# SMC_FrontPanel_ExtensionBoardV8_SMD.net
KiCad netlist of a schematic drawn in EAGLE
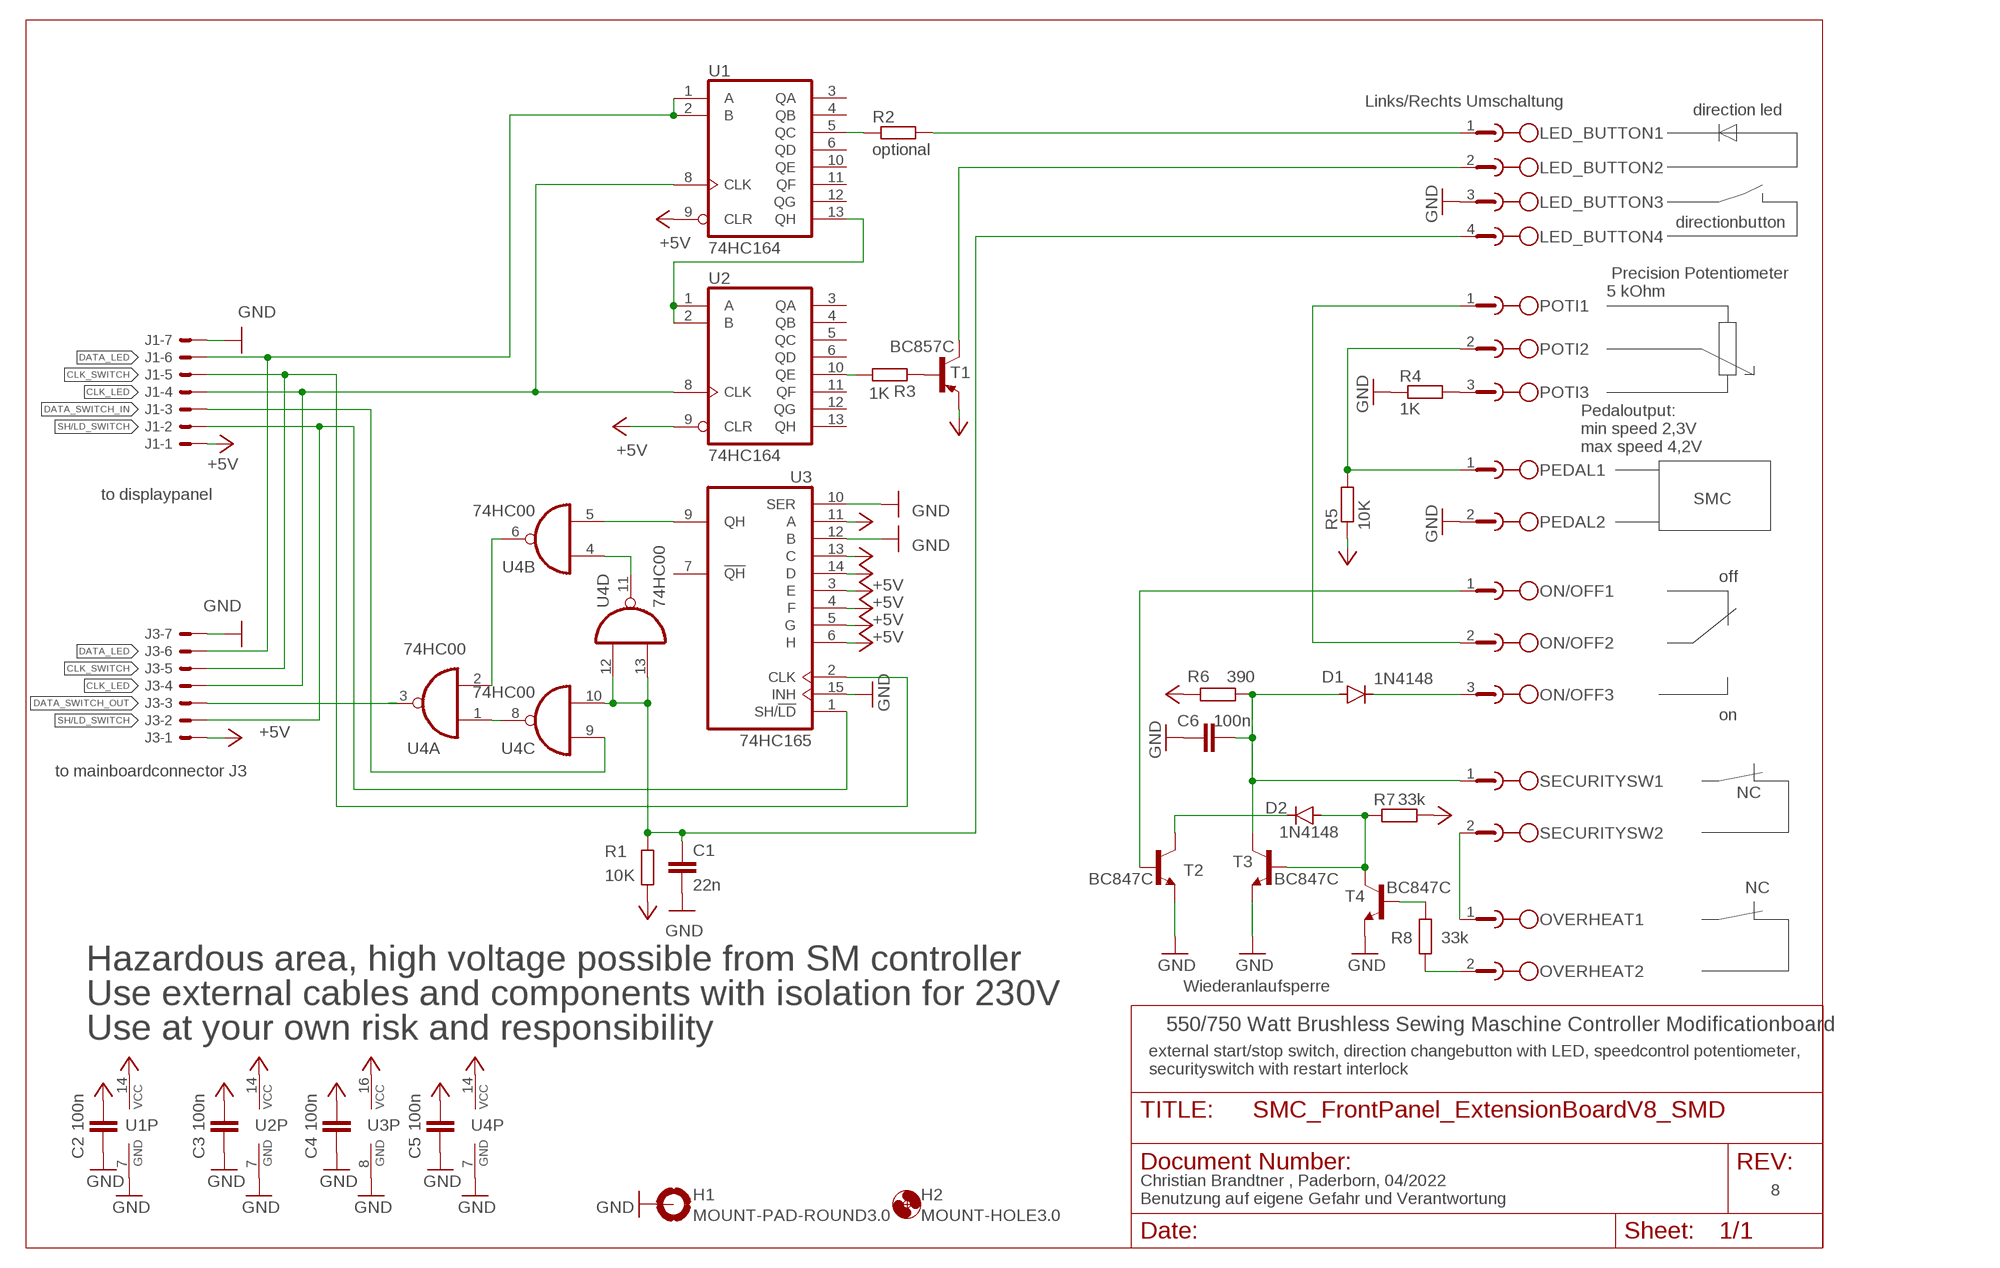
[diagram p0: schematic, sheet 1]

(export (version "E")
  (design (tool "Eeschema 10.0.6"))
  (components
    (comp (ref "C1")
      (value "22n")
      (footprint "eagle-import:C0805")
      (libsource (lib "eagle-import") (part "C-EUC0805"))
    )
    (comp (ref "C2")
      (value "100n")
      (footprint "eagle-import:C0805")
      (libsource (lib "eagle-import") (part "C-EUC0805"))
    )
    (comp (ref "C3")
      (value "100n")
      (footprint "eagle-import:C0805")
      (libsource (lib "eagle-import") (part "C-EUC0805"))
    )
    (comp (ref "C4")
      (value "100n")
      (footprint "eagle-import:C0805")
      (libsource (lib "eagle-import") (part "C-EUC0805"))
    )
    (comp (ref "C5")
      (value "100n")
      (footprint "eagle-import:C0805")
      (libsource (lib "eagle-import") (part "C-EUC0805"))
    )
    (comp (ref "C6")
      (value "100n")
      (footprint "eagle-import:C0805")
      (libsource (lib "eagle-import") (part "C-EUC0805"))
    )
    (comp (ref "D1")
      (value "1N4148")
      (footprint "eagle-import:SOD323-W")
      (libsource (lib "eagle-import") (part "DIODE-SOD323-W"))
    )
    (comp (ref "D2")
      (value "1N4148")
      (footprint "eagle-import:SOD323-W")
      (libsource (lib "eagle-import") (part "DIODE-SOD323-W"))
    )
    (comp (ref "H1")
      (value "MOUNT-PAD-ROUND3.0")
      (footprint "eagle-import:3,0-PAD")
      (libsource (lib "eagle-import") (part "MOUNT-PAD-ROUND3.0"))
    )
    (comp (ref "H2")
      (value "MOUNT-HOLE3.0")
      (footprint "eagle-import:3,0")
      (libsource (lib "eagle-import") (part "MOUNT-HOLE3.0"))
    )
    (comp (ref "J1")
      (value "to displaypanel")
      (footprint "eagle-import:JST-XH-07-PACKAGE-ROUND-PAD")
      (libsource (lib "eagle-import") (part "JST-XH-07-PIN-ROUND-PAD"))
    )
    (comp (ref "J3")
      (value "to mainboardconnector J3")
      (footprint "eagle-import:JST-XH-07-PACKAGE-ROUND-PAD")
      (libsource (lib "eagle-import") (part "JST-XH-07-PIN-ROUND-PAD"))
    )
    (comp (ref "LED_BUTTON")
      (value "MC_1.5/4_G_3.5")
      (footprint "eagle-import:MC_1.5_4-G-3.5")
      (libsource (lib "eagle-import") (part "MC_1.5/4_G_3.5"))
    )
    (comp (ref "ON/OFF")
      (value "MC_1.5/3-G-3.5")
      (footprint "eagle-import:MC_1.5_3-G-3.5")
      (libsource (lib "eagle-import") (part "MC_1.5/3-G-3.5"))
    )
    (comp (ref "OVERHEAT")
      (value "MC_1.5/2-G-3.5")
      (footprint "eagle-import:MC_1.5_2-G-3.5")
      (libsource (lib "eagle-import") (part "MC_1.5/2-G-3.5"))
    )
    (comp (ref "PEDAL")
      (value "MC_1.5/2-G-3.5")
      (footprint "eagle-import:MC_1.5_2-G-3.5")
      (libsource (lib "eagle-import") (part "MC_1.5/2-G-3.5"))
    )
    (comp (ref "POTI")
      (value "MC_1.5/3-G-3.5")
      (footprint "eagle-import:MC_1.5_3-G-3.5")
      (libsource (lib "eagle-import") (part "MC_1.5/3-G-3.5"))
    )
    (comp (ref "R1")
      (value "10K")
      (footprint "eagle-import:R0805")
      (libsource (lib "eagle-import") (part "R-EU_R0805"))
    )
    (comp (ref "R2")
      (value "optional")
      (footprint "eagle-import:R0805")
      (libsource (lib "eagle-import") (part "R-EU_R0805"))
    )
    (comp (ref "R3")
      (value "1K")
      (footprint "eagle-import:R0805")
      (libsource (lib "eagle-import") (part "R-EU_R0805"))
    )
    (comp (ref "R4")
      (value "1K")
      (footprint "eagle-import:R0805")
      (libsource (lib "eagle-import") (part "R-EU_R0805"))
    )
    (comp (ref "R5")
      (value "10K")
      (footprint "eagle-import:R0805")
      (libsource (lib "eagle-import") (part "R-EU_R0805"))
    )
    (comp (ref "R6")
      (value "390")
      (footprint "eagle-import:R0805")
      (libsource (lib "eagle-import") (part "R-EU_R0805"))
    )
    (comp (ref "R7")
      (value "33k")
      (footprint "eagle-import:R0805")
      (libsource (lib "eagle-import") (part "R-EU_R0805"))
    )
    (comp (ref "R8")
      (value "33k")
      (footprint "eagle-import:R0805")
      (libsource (lib "eagle-import") (part "R-EU_R0805"))
    )
    (comp (ref "SECURITYSW")
      (value "MC_1.5/2-G-3.5")
      (footprint "eagle-import:MC_1.5_2-G-3.5")
      (libsource (lib "eagle-import") (part "MC_1.5/2-G-3.5"))
    )
    (comp (ref "T1")
      (value "BC857C")
      (footprint "eagle-import:SOT23-BEC")
      (libsource (lib "eagle-import") (part "-PNP-SOT23-BECBC857C"))
    )
    (comp (ref "T2")
      (value "BC847C")
      (footprint "eagle-import:SOT23-BEC")
      (libsource (lib "eagle-import") (part "-NPN-SOT23-BECBC847C"))
    )
    (comp (ref "T3")
      (value "BC847C")
      (footprint "eagle-import:SOT23-BEC")
      (libsource (lib "eagle-import") (part "-NPN-SOT23-BECBC847C"))
    )
    (comp (ref "T4")
      (value "BC847C")
      (footprint "eagle-import:SOT23-BEC")
      (libsource (lib "eagle-import") (part "-NPN-SOT23-BECBC847C"))
    )
    (comp (ref "U1")
      (value "74HC164")
      (footprint "eagle-import:SO14")
      (libsource (lib "eagle-import") (part "74164DHC"))
    )
    (comp (ref "U2")
      (value "74HC164")
      (footprint "eagle-import:SO14")
      (libsource (lib "eagle-import") (part "74164DHC"))
    )
    (comp (ref "U3")
      (value "74HC165")
      (footprint "eagle-import:SO16")
      (libsource (lib "eagle-import") (part "74165DHC"))
    )
    (comp (ref "U4")
      (value "74HC00")
      (footprint "eagle-import:SO14")
      (libsource (lib "eagle-import") (part "7400DHC"))
    )
  )
  (nets
    (net (code "1") (name "+5V") (class "Default")
      (node (ref "C2") (pin "2") (pinfunction "2_2") (pintype "passive"))
      (node (ref "C3") (pin "2") (pinfunction "2_2") (pintype "passive"))
      (node (ref "C4") (pin "2") (pinfunction "2_2") (pintype "passive"))
      (node (ref "C5") (pin "2") (pinfunction "2_2") (pintype "passive"))
      (node (ref "J1") (pin "1") (pinfunction "S_1") (pintype "passive"))
      (node (ref "J3") (pin "1") (pinfunction "S_1") (pintype "passive"))
      (node (ref "R1") (pin "2") (pinfunction "2_2") (pintype "passive"))
      (node (ref "R5") (pin "1") (pinfunction "1_1") (pintype "passive"))
      (node (ref "R6") (pin "2") (pinfunction "2_2") (pintype "passive"))
      (node (ref "R7") (pin "1") (pinfunction "1_1") (pintype "passive"))
      (node (ref "T1") (pin "E") (pinfunction "E_E") (pintype "passive"))
      (node (ref "U1") (pin "14") (pinfunction "VCC_14") (pintype "power_in"))
      (node (ref "U1") (pin "9") (pinfunction "CLR_9") (pintype "input"))
      (node (ref "U2") (pin "14") (pinfunction "VCC_14") (pintype "power_in"))
      (node (ref "U2") (pin "9") (pinfunction "CLR_9") (pintype "input"))
      (node (ref "U3") (pin "11") (pinfunction "A_11") (pintype "input"))
      (node (ref "U3") (pin "13") (pinfunction "C_13") (pintype "input"))
      (node (ref "U3") (pin "14") (pinfunction "D_14") (pintype "input"))
      (node (ref "U3") (pin "16") (pinfunction "VCC_16") (pintype "power_in"))
      (node (ref "U3") (pin "3") (pinfunction "E_3") (pintype "input"))
      (node (ref "U3") (pin "4") (pinfunction "F_4") (pintype "input"))
      (node (ref "U3") (pin "5") (pinfunction "G_5") (pintype "input"))
      (node (ref "U3") (pin "6") (pinfunction "H_6") (pintype "input"))
      (node (ref "U4") (pin "14") (pinfunction "VCC_14") (pintype "power_in"))
    )
    (net (code "2") (name "CLK_LED") (class "Default")
      (node (ref "J1") (pin "4") (pinfunction "S_4") (pintype "passive"))
      (node (ref "J3") (pin "4") (pinfunction "S_4") (pintype "passive"))
      (node (ref "U1") (pin "8") (pinfunction "CLK_8") (pintype "input"))
      (node (ref "U2") (pin "8") (pinfunction "CLK_8") (pintype "input"))
    )
    (net (code "3") (name "CLK_SWITCH") (class "Default")
      (node (ref "J1") (pin "5") (pinfunction "S_5") (pintype "passive"))
      (node (ref "J3") (pin "5") (pinfunction "S_5") (pintype "passive"))
      (node (ref "U3") (pin "2") (pinfunction "CLK_2") (pintype "input"))
    )
    (net (code "4") (name "DATA_LED") (class "Default")
      (node (ref "J1") (pin "6") (pinfunction "S_6") (pintype "passive"))
      (node (ref "J3") (pin "6") (pinfunction "S_6") (pintype "passive"))
      (node (ref "U1") (pin "1") (pinfunction "A_1") (pintype "input"))
      (node (ref "U1") (pin "2") (pinfunction "B_2") (pintype "input"))
    )
    (net (code "5") (name "DATA_SWITCH_IN") (class "Default")
      (node (ref "J1") (pin "3") (pinfunction "S_3") (pintype "passive"))
      (node (ref "U4") (pin "9") (pinfunction "I0_9") (pintype "input"))
    )
    (net (code "6") (name "DATA_SWITCH_OUT") (class "Default")
      (node (ref "J3") (pin "3") (pinfunction "S_3") (pintype "passive"))
      (node (ref "U4") (pin "3") (pinfunction "O_3") (pintype "output"))
    )
    (net (code "7") (name "GND") (class "Default")
      (node (ref "C1") (pin "2") (pinfunction "2_2") (pintype "passive"))
      (node (ref "C2") (pin "1") (pinfunction "1_1") (pintype "passive"))
      (node (ref "C3") (pin "1") (pinfunction "1_1") (pintype "passive"))
      (node (ref "C4") (pin "1") (pinfunction "1_1") (pintype "passive"))
      (node (ref "C5") (pin "1") (pinfunction "1_1") (pintype "passive"))
      (node (ref "C6") (pin "1") (pinfunction "1_1") (pintype "passive"))
      (node (ref "H1") (pin "B3,0") (pinfunction "MOUNT_B3,0") (pintype "passive"))
      (node (ref "J1") (pin "7") (pinfunction "S_7") (pintype "passive"))
      (node (ref "J3") (pin "7") (pinfunction "S_7") (pintype "passive"))
      (node (ref "LED_BUTTON") (pin "3") (pinfunction "1_3") (pintype "passive"))
      (node (ref "PEDAL") (pin "2") (pinfunction "1_2") (pintype "passive"))
      (node (ref "R4") (pin "1") (pinfunction "1_1") (pintype "passive"))
      (node (ref "T2") (pin "E") (pinfunction "E_E") (pintype "passive"))
      (node (ref "T3") (pin "E") (pinfunction "E_E") (pintype "passive"))
      (node (ref "T4") (pin "E") (pinfunction "E_E") (pintype "passive"))
      (node (ref "U1") (pin "7") (pinfunction "GND_7") (pintype "power_in"))
      (node (ref "U2") (pin "7") (pinfunction "GND_7") (pintype "power_in"))
      (node (ref "U3") (pin "10") (pinfunction "SER_10") (pintype "input"))
      (node (ref "U3") (pin "12") (pinfunction "B_12") (pintype "input"))
      (node (ref "U3") (pin "15") (pinfunction "INH_15") (pintype "input"))
      (node (ref "U3") (pin "8") (pinfunction "GND_8") (pintype "power_in"))
      (node (ref "U4") (pin "7") (pinfunction "GND_7") (pintype "power_in"))
    )
    (net (code "8") (name "Net-(C6-Pad2)") (class "Default")
      (node (ref "C6") (pin "2") (pinfunction "2_2") (pintype "passive"))
      (node (ref "D1") (pin "A") (pinfunction "A_A") (pintype "passive"))
      (node (ref "R6") (pin "1") (pinfunction "1_1") (pintype "passive"))
      (node (ref "SECURITYSW") (pin "1") (pinfunction "1_1") (pintype "passive"))
      (node (ref "T3") (pin "C") (pinfunction "C_C") (pintype "passive"))
    )
    (net (code "9") (name "Net-(D2-PadA)") (class "Default")
      (node (ref "D2") (pin "A") (pinfunction "A_A") (pintype "passive"))
      (node (ref "R7") (pin "2") (pinfunction "2_2") (pintype "passive"))
      (node (ref "T3") (pin "B") (pinfunction "B_B") (pintype "passive"))
      (node (ref "T4") (pin "C") (pinfunction "C_C") (pintype "passive"))
    )
    (net (code "10") (name "Net-(D2-PadC)") (class "Default")
      (node (ref "D2") (pin "C") (pinfunction "C_C") (pintype "passive"))
      (node (ref "T2") (pin "C") (pinfunction "C_C") (pintype "passive"))
    )
    (net (code "11") (name "Net-(LED_BUTTON-Pad1)") (class "Default")
      (node (ref "LED_BUTTON") (pin "1") (pinfunction "1_1") (pintype "passive"))
      (node (ref "R2") (pin "2") (pinfunction "2_2") (pintype "passive"))
    )
    (net (code "12") (name "Net-(LED_BUTTONB-1)") (class "Default")
      (node (ref "LED_BUTTON") (pin "2") (pinfunction "1_2") (pintype "passive"))
      (node (ref "T1") (pin "C") (pinfunction "C_C") (pintype "passive"))
    )
    (net (code "13") (name "Net-(LED_BUTTOND-1)") (class "Default")
      (node (ref "C1") (pin "1") (pinfunction "1_1") (pintype "passive"))
      (node (ref "LED_BUTTON") (pin "4") (pinfunction "1_4") (pintype "passive"))
      (node (ref "R1") (pin "1") (pinfunction "1_1") (pintype "passive"))
      (node (ref "U4") (pin "10") (pinfunction "I1_10") (pintype "input"))
      (node (ref "U4") (pin "12") (pinfunction "I0_12") (pintype "input"))
      (node (ref "U4") (pin "13") (pinfunction "I1_13") (pintype "input"))
    )
    (net (code "14") (name "Net-(ON/OFF-Pad1)") (class "Default")
      (node (ref "ON/OFF") (pin "1") (pinfunction "1_1") (pintype "passive"))
      (node (ref "T2") (pin "B") (pinfunction "B_B") (pintype "passive"))
    )
    (net (code "15") (name "Net-(ON/OFFB-1)") (class "Default")
      (node (ref "ON/OFF") (pin "2") (pinfunction "1_2") (pintype "passive"))
      (node (ref "POTI") (pin "1") (pinfunction "1_1") (pintype "passive"))
    )
    (net (code "16") (name "Net-(ON/OFFC-1)") (class "Default")
      (node (ref "D1") (pin "C") (pinfunction "C_C") (pintype "passive"))
      (node (ref "ON/OFF") (pin "3") (pinfunction "1_3") (pintype "passive"))
    )
    (net (code "17") (name "Net-(OVERHEATB-1)") (class "Default")
      (node (ref "OVERHEAT") (pin "2") (pinfunction "1_2") (pintype "passive"))
      (node (ref "R8") (pin "2") (pinfunction "2_2") (pintype "passive"))
    )
    (net (code "18") (name "Net-(POTIB-1)") (class "Default")
      (node (ref "PEDAL") (pin "1") (pinfunction "1_1") (pintype "passive"))
      (node (ref "POTI") (pin "2") (pinfunction "1_2") (pintype "passive"))
      (node (ref "R5") (pin "2") (pinfunction "2_2") (pintype "passive"))
    )
    (net (code "19") (name "Net-(POTIC-1)") (class "Default")
      (node (ref "POTI") (pin "3") (pinfunction "1_3") (pintype "passive"))
      (node (ref "R4") (pin "2") (pinfunction "2_2") (pintype "passive"))
    )
    (net (code "20") (name "Net-(R3-Pad1)") (class "Default")
      (node (ref "R3") (pin "1") (pinfunction "1_1") (pintype "passive"))
      (node (ref "T1") (pin "B") (pinfunction "B_B") (pintype "passive"))
    )
    (net (code "21") (name "Net-(R8-Pad1)") (class "Default")
      (node (ref "R8") (pin "1") (pinfunction "1_1") (pintype "passive"))
      (node (ref "T4") (pin "B") (pinfunction "B_B") (pintype "passive"))
    )
    (net (code "22") (name "Net-(SECURITYSWB-1)") (class "Default")
      (node (ref "OVERHEAT") (pin "1") (pinfunction "1_1") (pintype "passive"))
      (node (ref "SECURITYSW") (pin "2") (pinfunction "1_2") (pintype "passive"))
    )
    (net (code "23") (name "Net-(U1A-QC)") (class "Default")
      (node (ref "R2") (pin "1") (pinfunction "1_1") (pintype "passive"))
      (node (ref "U1") (pin "5") (pinfunction "QC_5") (pintype "output"))
    )
    (net (code "24") (name "Net-(U1A-QH)") (class "Default")
      (node (ref "U1") (pin "13") (pinfunction "QH_13") (pintype "output"))
      (node (ref "U2") (pin "1") (pinfunction "A_1") (pintype "input"))
      (node (ref "U2") (pin "2") (pinfunction "B_2") (pintype "input"))
    )
    (net (code "25") (name "Net-(U2A-QE)") (class "Default")
      (node (ref "R3") (pin "2") (pinfunction "2_2") (pintype "passive"))
      (node (ref "U2") (pin "10") (pinfunction "QE_10") (pintype "output"))
    )
    (net (code "26") (name "Net-(U3A-QH)") (class "Default")
      (node (ref "U3") (pin "9") (pinfunction "QH_9") (pintype "output"))
      (node (ref "U4") (pin "5") (pinfunction "I1_5") (pintype "input"))
    )
    (net (code "27") (name "Net-(U4A-I0)") (class "Default")
      (node (ref "U4") (pin "1") (pinfunction "I0_1") (pintype "input"))
      (node (ref "U4") (pin "8") (pinfunction "O_8") (pintype "output"))
    )
    (net (code "28") (name "Net-(U4A-I1)") (class "Default")
      (node (ref "U4") (pin "2") (pinfunction "I1_2") (pintype "input"))
      (node (ref "U4") (pin "6") (pinfunction "O_6") (pintype "output"))
    )
    (net (code "29") (name "Net-(U4B-I0)") (class "Default")
      (node (ref "U4") (pin "11") (pinfunction "O_11") (pintype "output"))
      (node (ref "U4") (pin "4") (pinfunction "I0_4") (pintype "input"))
    )
    (net (code "30") (name "SH{slash}LD_SWITCH") (class "Default")
      (node (ref "J1") (pin "2") (pinfunction "S_2") (pintype "passive"))
      (node (ref "J3") (pin "2") (pinfunction "S_2") (pintype "passive"))
      (node (ref "U3") (pin "1") (pinfunction "SH/~{LD}_1") (pintype "input"))
    )
    (net (code "31") (name "unconnected-(U1A-QA-Pad3)") (class "Default")
      (node (ref "U1") (pin "3") (pinfunction "QA_3") (pintype "output"))
    )
    (net (code "32") (name "unconnected-(U1A-QB-Pad4)") (class "Default")
      (node (ref "U1") (pin "4") (pinfunction "QB_4") (pintype "output"))
    )
    (net (code "33") (name "unconnected-(U1A-QD-Pad6)") (class "Default")
      (node (ref "U1") (pin "6") (pinfunction "QD_6") (pintype "output"))
    )
    (net (code "34") (name "unconnected-(U1A-QE-Pad10)") (class "Default")
      (node (ref "U1") (pin "10") (pinfunction "QE_10") (pintype "output"))
    )
    (net (code "35") (name "unconnected-(U1A-QF-Pad11)") (class "Default")
      (node (ref "U1") (pin "11") (pinfunction "QF_11") (pintype "output"))
    )
    (net (code "36") (name "unconnected-(U1A-QG-Pad12)") (class "Default")
      (node (ref "U1") (pin "12") (pinfunction "QG_12") (pintype "output"))
    )
    (net (code "37") (name "unconnected-(U2A-QA-Pad3)") (class "Default")
      (node (ref "U2") (pin "3") (pinfunction "QA_3") (pintype "output"))
    )
    (net (code "38") (name "unconnected-(U2A-QB-Pad4)") (class "Default")
      (node (ref "U2") (pin "4") (pinfunction "QB_4") (pintype "output"))
    )
    (net (code "39") (name "unconnected-(U2A-QC-Pad5)") (class "Default")
      (node (ref "U2") (pin "5") (pinfunction "QC_5") (pintype "output"))
    )
    (net (code "40") (name "unconnected-(U2A-QD-Pad6)") (class "Default")
      (node (ref "U2") (pin "6") (pinfunction "QD_6") (pintype "output"))
    )
    (net (code "41") (name "unconnected-(U2A-QF-Pad11)") (class "Default")
      (node (ref "U2") (pin "11") (pinfunction "QF_11") (pintype "output"))
    )
    (net (code "42") (name "unconnected-(U2A-QG-Pad12)") (class "Default")
      (node (ref "U2") (pin "12") (pinfunction "QG_12") (pintype "output"))
    )
    (net (code "43") (name "unconnected-(U2A-QH-Pad13)") (class "Default")
      (node (ref "U2") (pin "13") (pinfunction "QH_13") (pintype "output"))
    )
    (net (code "44") (name "unconnected-(U3A-~{QH}-Pad7)") (class "Default")
      (node (ref "U3") (pin "7") (pinfunction "~{QH}_7") (pintype "output"))
    )
  )
)
